# pigtrotr.net
KiCad netlist of a schematic drawn in EAGLE
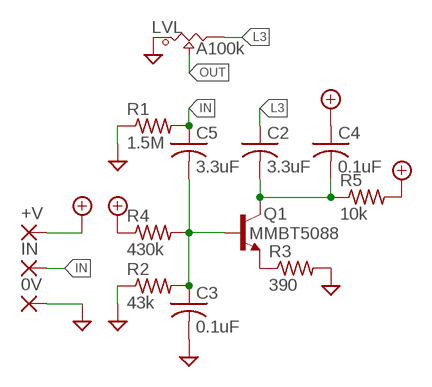
[diagram p0: schematic, sheet 1]

(export (version "E")
  (design (tool "Eeschema 10.0.6"))
  (components
    (comp (ref "+V")
      (value "SMD2")
      (footprint "eagle-import:SMD1,27-2,54")
      (libsource (lib "eagle-import") (part "SMD2"))
    )
    (comp (ref "0V")
      (value "SMD2")
      (footprint "eagle-import:SMD1,27-2,54")
      (libsource (lib "eagle-import") (part "SMD2"))
    )
    (comp (ref "C2")
      (value "3.3uF")
      (footprint "eagle-import:C0805")
      (libsource (lib "eagle-import") (part "C-USC0805"))
    )
    (comp (ref "C3")
      (value "0.1uF")
      (footprint "eagle-import:C0603")
      (libsource (lib "eagle-import") (part "C-USC0603"))
    )
    (comp (ref "C4")
      (value "0.1uF")
      (footprint "eagle-import:C0603")
      (libsource (lib "eagle-import") (part "C-USC0603"))
    )
    (comp (ref "C5")
      (value "3.3uF")
      (footprint "eagle-import:C1206")
      (libsource (lib "eagle-import") (part "C-USC1206"))
    )
    (comp (ref "IN")
      (value "SMD2")
      (footprint "eagle-import:SMD1,27-2,54")
      (libsource (lib "eagle-import") (part "SMD2"))
    )
    (comp (ref "LVL")
      (value "A100k")
      (footprint "eagle-import:POT_9MM_SMD")
      (libsource (lib "eagle-import") (part "POT_9MM_SMD"))
    )
    (comp (ref "Q1")
      (value "MMBT5088")
      (footprint "eagle-import:SOT23-BEC")
      (fields (field (name "MF") "ON Semiconductor"))
      (libsource (lib "eagle-import") (part "MMBT5088"))
    )
    (comp (ref "R1")
      (value "1.5M")
      (footprint "eagle-import:R0603")
      (libsource (lib "eagle-import") (part "R-US_R0603"))
    )
    (comp (ref "R2")
      (value "43k")
      (footprint "eagle-import:R0603")
      (libsource (lib "eagle-import") (part "R-US_R0603"))
    )
    (comp (ref "R3")
      (value "390")
      (footprint "eagle-import:R0603")
      (libsource (lib "eagle-import") (part "R-US_R0603"))
    )
    (comp (ref "R4")
      (value "430k")
      (footprint "eagle-import:R0603")
      (libsource (lib "eagle-import") (part "R-US_R0603"))
    )
    (comp (ref "R5")
      (value "10k")
      (footprint "eagle-import:R0603")
      (libsource (lib "eagle-import") (part "R-US_R0603"))
    )
  )
  (nets
    (net (code "1") (name "+9V") (class "Default")
      (node (ref "+V") (pin "1") (pinfunction "P_1") (pintype "passive"))
      (node (ref "C4") (pin "1") (pinfunction "1_1") (pintype "passive"))
      (node (ref "R4") (pin "1") (pinfunction "1_1") (pintype "passive"))
      (node (ref "R5") (pin "2") (pinfunction "2_2") (pintype "passive"))
    )
    (net (code "2") (name "GND") (class "Default")
      (node (ref "0V") (pin "1") (pinfunction "P_1") (pintype "passive"))
      (node (ref "C3") (pin "2") (pinfunction "2_2") (pintype "passive"))
      (node (ref "LVL") (pin "1") (pinfunction "1_1") (pintype "bidirectional"))
      (node (ref "R1") (pin "1") (pinfunction "1_1") (pintype "passive"))
      (node (ref "R2") (pin "1") (pinfunction "1_1") (pintype "passive"))
      (node (ref "R3") (pin "2") (pinfunction "2_2") (pintype "passive"))
    )
    (net (code "3") (name "IN") (class "Default")
      (node (ref "C5") (pin "1") (pinfunction "1_1") (pintype "passive"))
      (node (ref "IN") (pin "1") (pinfunction "P_1") (pintype "passive"))
      (node (ref "R1") (pin "2") (pinfunction "2_2") (pintype "passive"))
    )
    (net (code "4") (name "L3") (class "Default")
      (node (ref "C2") (pin "1") (pinfunction "1_1") (pintype "passive"))
      (node (ref "LVL") (pin "3") (pinfunction "3_3") (pintype "bidirectional"))
    )
    (net (code "5") (name "Net-(C2-Pad2)") (class "Default")
      (node (ref "C2") (pin "2") (pinfunction "2_2") (pintype "passive"))
      (node (ref "C4") (pin "2") (pinfunction "2_2") (pintype "passive"))
      (node (ref "Q1") (pin "C") (pinfunction "C_C") (pintype "passive"))
      (node (ref "R5") (pin "1") (pinfunction "1_1") (pintype "passive"))
    )
    (net (code "6") (name "Net-(C3-Pad1)") (class "Default")
      (node (ref "C3") (pin "1") (pinfunction "1_1") (pintype "passive"))
      (node (ref "C5") (pin "2") (pinfunction "2_2") (pintype "passive"))
      (node (ref "Q1") (pin "B") (pinfunction "B_B") (pintype "passive"))
      (node (ref "R2") (pin "2") (pinfunction "2_2") (pintype "passive"))
      (node (ref "R4") (pin "2") (pinfunction "2_2") (pintype "passive"))
    )
    (net (code "7") (name "Net-(Q1-PadE)") (class "Default")
      (node (ref "Q1") (pin "E") (pinfunction "E_E") (pintype "passive"))
      (node (ref "R3") (pin "1") (pinfunction "1_1") (pintype "passive"))
    )
    (net (code "8") (name "OUT") (class "Default")
      (node (ref "LVL") (pin "2") (pinfunction "2_2") (pintype "bidirectional"))
    )
  )
)
